# CDCEmu_Logic_v2_1.net
KiCad netlist of a schematic drawn in EAGLE
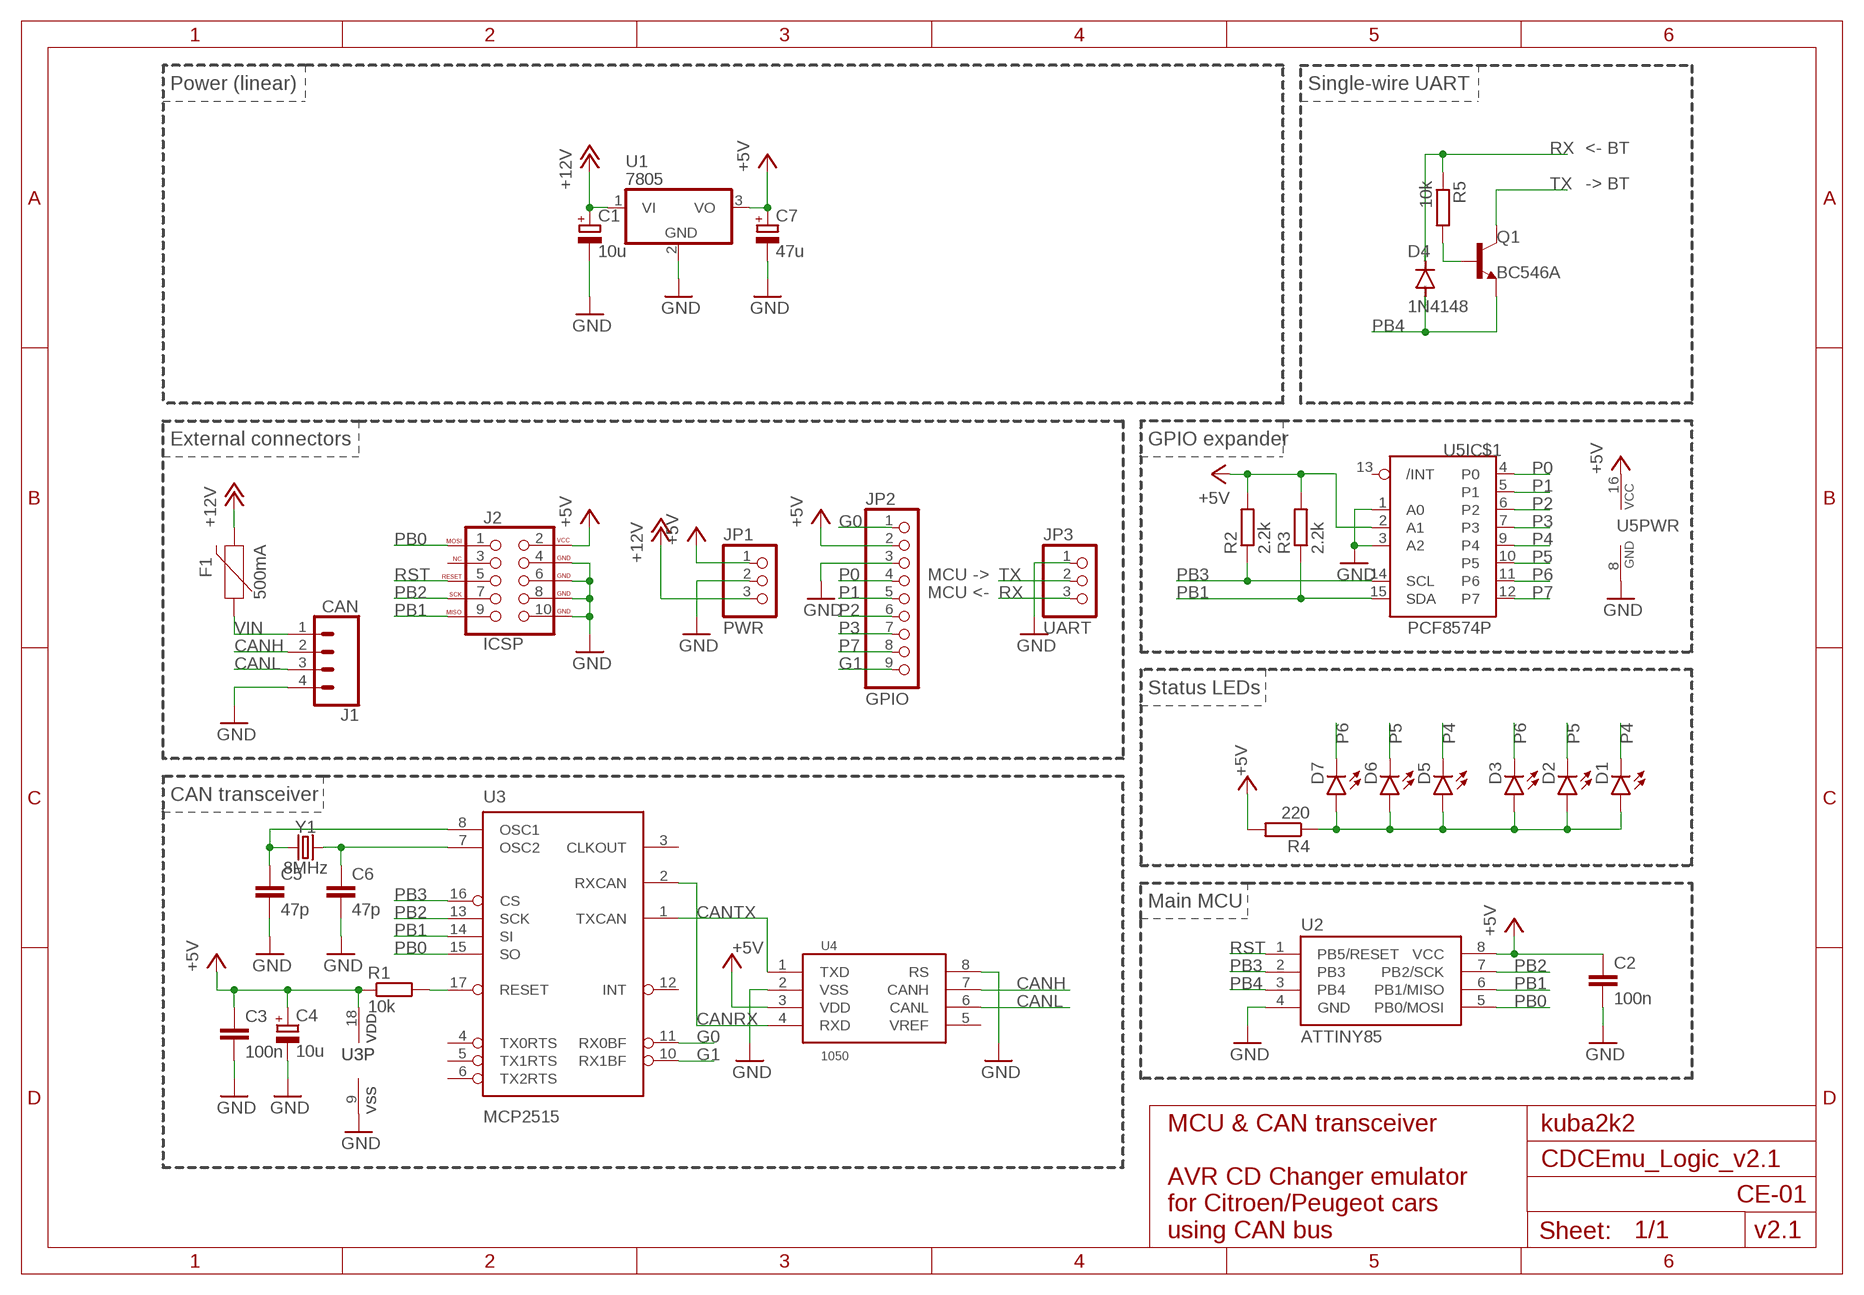
[diagram p0: schematic, sheet 1]

(export (version "E")
  (design (tool "Eeschema 10.0.6"))
  (components
    (comp (ref "C1")
      (value "10u")
      (footprint "eagle-import:C2512-POL")
      (libsource (lib "eagle-import") (part "CPOL-EUC2512"))
    )
    (comp (ref "C2")
      (value "100n")
      (footprint "eagle-import:C050-024X044")
      (libsource (lib "eagle-import") (part "C-EU050-024X044"))
    )
    (comp (ref "C3")
      (value "100n")
      (footprint "eagle-import:C050-024X044")
      (libsource (lib "eagle-import") (part "C-EU050-024X044"))
    )
    (comp (ref "C4")
      (value "10u")
      (footprint "eagle-import:E2,5-6")
      (libsource (lib "eagle-import") (part "CPOL-EUE2.5-6"))
    )
    (comp (ref "C5")
      (value "47p")
      (footprint "eagle-import:C0805")
      (libsource (lib "eagle-import") (part "C-EUC0805"))
    )
    (comp (ref "C6")
      (value "47p")
      (footprint "eagle-import:C0805")
      (libsource (lib "eagle-import") (part "C-EUC0805"))
    )
    (comp (ref "C7")
      (value "47u")
      (footprint "eagle-import:C2512-POL")
      (libsource (lib "eagle-import") (part "CPOL-EUC2512"))
    )
    (comp (ref "D1")
      (value "LED3MM")
      (footprint "eagle-import:LED3MM")
      (libsource (lib "eagle-import") (part "LED3MM"))
    )
    (comp (ref "D2")
      (value "LED3MM")
      (footprint "eagle-import:LED3MM")
      (libsource (lib "eagle-import") (part "LED3MM"))
    )
    (comp (ref "D3")
      (value "LED3MM")
      (footprint "eagle-import:LED3MM")
      (libsource (lib "eagle-import") (part "LED3MM"))
    )
    (comp (ref "D4")
      (value "1N4148")
      (footprint "eagle-import:DO35-7")
      (libsource (lib "eagle-import") (part "1N4148DO35-7"))
    )
    (comp (ref "D5")
      (value "LEDCHIP-LED0805")
      (footprint "eagle-import:CHIP-LED0805")
      (libsource (lib "eagle-import") (part "LEDCHIP-LED0805"))
    )
    (comp (ref "D6")
      (value "LEDCHIP-LED0805")
      (footprint "eagle-import:CHIP-LED0805")
      (libsource (lib "eagle-import") (part "LEDCHIP-LED0805"))
    )
    (comp (ref "D7")
      (value "LEDCHIP-LED0805")
      (footprint "eagle-import:CHIP-LED0805")
      (libsource (lib "eagle-import") (part "LEDCHIP-LED0805"))
    )
    (comp (ref "F1")
      (value "500mA")
      (footprint "eagle-import:1812")
      (libsource (lib "eagle-import") (part "PPTC_16V_2.5A"))
    )
    (comp (ref "J1")
      (value "CAN")
      (footprint "eagle-import:JST-4-PTH")
      (libsource (lib "eagle-import") (part "CONN_04JST-PTH"))
    )
    (comp (ref "J2")
      (value "ICSP")
      (footprint "eagle-import:2X5-SHROUDED_LOCK")
      (libsource (lib "eagle-import") (part "AVR_SPI_PROG_5X2LOCK"))
    )
    (comp (ref "JP1")
      (value "PWR")
      (footprint "eagle-import:1X03")
      (libsource (lib "eagle-import") (part "PINHD-1X3"))
    )
    (comp (ref "JP2")
      (value "GPIO")
      (footprint "eagle-import:1X09")
      (libsource (lib "eagle-import") (part "PINHD-1X9"))
    )
    (comp (ref "JP3")
      (value "UART")
      (footprint "eagle-import:1X03")
      (libsource (lib "eagle-import") (part "PINHD-1X3"))
    )
    (comp (ref "Q1")
      (value "BC546A")
      (footprint "eagle-import:TO92-EBC")
      (libsource (lib "eagle-import") (part "BC546A"))
    )
    (comp (ref "R1")
      (value "10k")
      (footprint "eagle-import:R0805")
      (libsource (lib "eagle-import") (part "R-EU_R0805"))
    )
    (comp (ref "R2")
      (value "2.2k")
      (footprint "eagle-import:R0805")
      (libsource (lib "eagle-import") (part "R-EU_R0805"))
    )
    (comp (ref "R3")
      (value "2.2k")
      (footprint "eagle-import:R0805")
      (libsource (lib "eagle-import") (part "R-EU_R0805"))
    )
    (comp (ref "R4")
      (value "220")
      (footprint "eagle-import:0204_7")
      (libsource (lib "eagle-import") (part "R-EU_0204/7"))
    )
    (comp (ref "R5")
      (value "10k")
      (footprint "eagle-import:0204_7")
      (libsource (lib "eagle-import") (part "R-EU_0204/7"))
    )
    (comp (ref "U1")
      (value "7805")
      (footprint "eagle-import:TO220H-NOHOLE")
      (libsource (lib "eagle-import") (part "78T-NOHOLE"))
    )
    (comp (ref "U2")
      (value "ATTINY85")
      (footprint "eagle-import:PDIP08_300MIL")
      (libsource (lib "eagle-import") (part "ATTINY85P-"))
    )
    (comp (ref "U3")
      (value "MCP2515")
      (footprint "eagle-import:SO18W")
      (libsource (lib "eagle-import") (part "MCP2515(MCP2510)SO"))
    )
    (comp (ref "U4")
      (value "1050")
      (footprint "eagle-import:SO08")
      (libsource (lib "eagle-import") (part "TJA1050"))
    )
    (comp (ref "U5")
      (value "PCF8574P")
      (footprint "eagle-import:DIL16")
      (libsource (lib "eagle-import") (part "PCF8574P"))
    )
    (comp (ref "Y1")
      (value "8MHz")
      (footprint "eagle-import:HC49U")
      (libsource (lib "eagle-import") (part "CRYSTALPTH-HC49UV"))
    )
  )
  (nets
    (net (code "1") (name "+5V") (class "Default")
      (node (ref "C2") (pin "1") (pinfunction "1_1") (pintype "passive"))
      (node (ref "C3") (pin "1") (pinfunction "1_1") (pintype "passive"))
      (node (ref "C4") (pin "+") (pinfunction "+_+") (pintype "passive"))
      (node (ref "C7") (pin "+") (pinfunction "+_+") (pintype "passive"))
      (node (ref "J2") (pin "2") (pinfunction "VCC_2") (pintype "power_in"))
      (node (ref "JP1") (pin "1") (pinfunction "1_1") (pintype "passive"))
      (node (ref "JP2") (pin "2") (pinfunction "2_2") (pintype "passive"))
      (node (ref "R1") (pin "1") (pinfunction "1_1") (pintype "passive"))
      (node (ref "R2") (pin "2") (pinfunction "2_2") (pintype "passive"))
      (node (ref "R3") (pin "2") (pinfunction "2_2") (pintype "passive"))
      (node (ref "R4") (pin "2") (pinfunction "2_2") (pintype "passive"))
      (node (ref "U1") (pin "3") (pinfunction "VO_3") (pintype "passive"))
      (node (ref "U2") (pin "8") (pinfunction "VCC_8") (pintype "power_in"))
      (node (ref "U3") (pin "18") (pinfunction "VDD_18") (pintype "power_in"))
      (node (ref "U4") (pin "3") (pinfunction "VDD_3") (pintype "power_in"))
      (node (ref "U5") (pin "16") (pinfunction "VCC_16") (pintype "power_in"))
      (node (ref "U5") (pin "2") (pinfunction "A1_2") (pintype "input"))
    )
    (net (code "2") (name "+12V") (class "Default")
      (node (ref "C1") (pin "+") (pinfunction "+_+") (pintype "passive"))
      (node (ref "F1") (pin "2") (pinfunction "2_2") (pintype "bidirectional"))
      (node (ref "JP1") (pin "3") (pinfunction "3_3") (pintype "passive"))
      (node (ref "U1") (pin "1") (pinfunction "VI_1") (pintype "input"))
    )
    (net (code "3") (name "/CANH") (class "Default")
      (node (ref "J1") (pin "2") (pinfunction "2_2") (pintype "passive"))
      (node (ref "U4") (pin "7") (pinfunction "CANH_7") (pintype "bidirectional"))
    )
    (net (code "4") (name "/CANL") (class "Default")
      (node (ref "J1") (pin "3") (pinfunction "3_3") (pintype "passive"))
      (node (ref "U4") (pin "6") (pinfunction "CANL_6") (pintype "bidirectional"))
    )
    (net (code "5") (name "/CANRX") (class "Default")
      (node (ref "U3") (pin "2") (pinfunction "RXCAN_2") (pintype "input"))
      (node (ref "U4") (pin "4") (pinfunction "RXD_4") (pintype "output"))
    )
    (net (code "6") (name "/CANTX") (class "Default")
      (node (ref "U3") (pin "1") (pinfunction "TXCAN_1") (pintype "output"))
      (node (ref "U4") (pin "1") (pinfunction "TXD_1") (pintype "input"))
    )
    (net (code "7") (name "/G0") (class "Default")
      (node (ref "JP2") (pin "1") (pinfunction "1_1") (pintype "passive"))
      (node (ref "U3") (pin "11") (pinfunction "RX0BF_11") (pintype "output"))
    )
    (net (code "8") (name "/G1") (class "Default")
      (node (ref "JP2") (pin "9") (pinfunction "9_9") (pintype "passive"))
      (node (ref "U3") (pin "10") (pinfunction "RX1BF_10") (pintype "output"))
    )
    (net (code "9") (name "/P0") (class "Default")
      (node (ref "JP2") (pin "4") (pinfunction "4_4") (pintype "passive"))
      (node (ref "U5") (pin "4") (pinfunction "P0_4") (pintype "bidirectional"))
    )
    (net (code "10") (name "/P1") (class "Default")
      (node (ref "JP2") (pin "5") (pinfunction "5_5") (pintype "passive"))
      (node (ref "U5") (pin "5") (pinfunction "P1_5") (pintype "bidirectional"))
    )
    (net (code "11") (name "/P2") (class "Default")
      (node (ref "JP2") (pin "6") (pinfunction "6_6") (pintype "passive"))
      (node (ref "U5") (pin "6") (pinfunction "P2_6") (pintype "bidirectional"))
    )
    (net (code "12") (name "/P3") (class "Default")
      (node (ref "JP2") (pin "7") (pinfunction "7_7") (pintype "passive"))
      (node (ref "U5") (pin "7") (pinfunction "P3_7") (pintype "bidirectional"))
    )
    (net (code "13") (name "/P4") (class "Default")
      (node (ref "D1") (pin "K") (pinfunction "C_K") (pintype "passive"))
      (node (ref "D5") (pin "C") (pinfunction "C_C") (pintype "passive"))
      (node (ref "U5") (pin "9") (pinfunction "P4_9") (pintype "bidirectional"))
    )
    (net (code "14") (name "/P5") (class "Default")
      (node (ref "D2") (pin "K") (pinfunction "C_K") (pintype "passive"))
      (node (ref "D6") (pin "C") (pinfunction "C_C") (pintype "passive"))
      (node (ref "U5") (pin "10") (pinfunction "P5_10") (pintype "bidirectional"))
    )
    (net (code "15") (name "/P6") (class "Default")
      (node (ref "D3") (pin "K") (pinfunction "C_K") (pintype "passive"))
      (node (ref "D7") (pin "C") (pinfunction "C_C") (pintype "passive"))
      (node (ref "U5") (pin "11") (pinfunction "P6_11") (pintype "bidirectional"))
    )
    (net (code "16") (name "/P7") (class "Default")
      (node (ref "JP2") (pin "8") (pinfunction "8_8") (pintype "passive"))
      (node (ref "U5") (pin "12") (pinfunction "P7_12") (pintype "bidirectional"))
    )
    (net (code "17") (name "/PB0") (class "Default")
      (node (ref "J2") (pin "1") (pinfunction "MOSI_1") (pintype "passive"))
      (node (ref "U2") (pin "5") (pinfunction "PB0/MOSI_5") (pintype "bidirectional"))
      (node (ref "U3") (pin "15") (pinfunction "SO_15") (pintype "output"))
    )
    (net (code "18") (name "/PB1") (class "Default")
      (node (ref "J2") (pin "9") (pinfunction "MISO_9") (pintype "passive"))
      (node (ref "R3") (pin "1") (pinfunction "1_1") (pintype "passive"))
      (node (ref "U2") (pin "6") (pinfunction "PB1/MISO_6") (pintype "bidirectional"))
      (node (ref "U3") (pin "14") (pinfunction "SI_14") (pintype "input"))
      (node (ref "U5") (pin "15") (pinfunction "SDA_15") (pintype "bidirectional"))
    )
    (net (code "19") (name "/PB2") (class "Default")
      (node (ref "J2") (pin "7") (pinfunction "SCK_7") (pintype "passive"))
      (node (ref "U2") (pin "7") (pinfunction "PB2/SCK_7") (pintype "bidirectional"))
      (node (ref "U3") (pin "13") (pinfunction "SCK_13") (pintype "input"))
    )
    (net (code "20") (name "/PB3") (class "Default")
      (node (ref "R2") (pin "1") (pinfunction "1_1") (pintype "passive"))
      (node (ref "U2") (pin "2") (pinfunction "PB3_2") (pintype "bidirectional"))
      (node (ref "U3") (pin "16") (pinfunction "CS_16") (pintype "input"))
      (node (ref "U5") (pin "14") (pinfunction "SCL_14") (pintype "input"))
    )
    (net (code "21") (name "/PB4") (class "Default")
      (node (ref "D4") (pin "A") (pinfunction "A_A") (pintype "passive"))
      (node (ref "Q1") (pin "E") (pinfunction "E_E") (pintype "passive"))
      (node (ref "U2") (pin "3") (pinfunction "PB4_3") (pintype "bidirectional"))
    )
    (net (code "22") (name "/RST") (class "Default")
      (node (ref "J2") (pin "5") (pinfunction "RESET_5") (pintype "passive"))
      (node (ref "U2") (pin "1") (pinfunction "PB5/RESET_1") (pintype "bidirectional"))
    )
    (net (code "23") (name "/RX") (class "Default")
      (node (ref "D4") (pin "C") (pinfunction "C_C") (pintype "passive"))
      (node (ref "JP3") (pin "3") (pinfunction "3_3") (pintype "passive"))
      (node (ref "R5") (pin "1") (pinfunction "1_1") (pintype "passive"))
    )
    (net (code "24") (name "/TX") (class "Default")
      (node (ref "JP3") (pin "2") (pinfunction "2_2") (pintype "passive"))
      (node (ref "Q1") (pin "C") (pinfunction "C_C") (pintype "passive"))
    )
    (net (code "25") (name "/VIN") (class "Default")
      (node (ref "F1") (pin "1") (pinfunction "1_1") (pintype "bidirectional"))
      (node (ref "J1") (pin "1") (pinfunction "1_1") (pintype "passive"))
    )
    (net (code "26") (name "GND") (class "Default")
      (node (ref "C1") (pin "-") (pinfunction "-_-") (pintype "passive"))
      (node (ref "C2") (pin "2") (pinfunction "2_2") (pintype "passive"))
      (node (ref "C3") (pin "2") (pinfunction "2_2") (pintype "passive"))
      (node (ref "C4") (pin "-") (pinfunction "-_-") (pintype "passive"))
      (node (ref "C5") (pin "2") (pinfunction "2_2") (pintype "passive"))
      (node (ref "C6") (pin "2") (pinfunction "2_2") (pintype "passive"))
      (node (ref "C7") (pin "-") (pinfunction "-_-") (pintype "passive"))
      (node (ref "J1") (pin "4") (pinfunction "4_4") (pintype "passive"))
      (node (ref "J2") (pin "10") (pinfunction "GND_10") (pintype "power_in"))
      (node (ref "J2") (pin "4") (pinfunction "GND_4") (pintype "power_in"))
      (node (ref "J2") (pin "6") (pinfunction "GND_6") (pintype "power_in"))
      (node (ref "J2") (pin "8") (pinfunction "GND_8") (pintype "power_in"))
      (node (ref "JP1") (pin "2") (pinfunction "2_2") (pintype "passive"))
      (node (ref "JP2") (pin "3") (pinfunction "3_3") (pintype "passive"))
      (node (ref "JP3") (pin "1") (pinfunction "1_1") (pintype "passive"))
      (node (ref "U1") (pin "2") (pinfunction "GND_2") (pintype "passive"))
      (node (ref "U2") (pin "4") (pinfunction "GND_4") (pintype "power_in"))
      (node (ref "U3") (pin "9") (pinfunction "VSS_9") (pintype "power_in"))
      (node (ref "U4") (pin "2") (pinfunction "VSS_2") (pintype "power_in"))
      (node (ref "U4") (pin "8") (pinfunction "RS_8") (pintype "input"))
      (node (ref "U5") (pin "1") (pinfunction "A0_1") (pintype "input"))
      (node (ref "U5") (pin "3") (pinfunction "A2_3") (pintype "input"))
      (node (ref "U5") (pin "8") (pinfunction "GND_8") (pintype "power_in"))
    )
    (net (code "27") (name "Net-(D1-PadA)") (class "Default")
      (node (ref "D1") (pin "A") (pinfunction "A_A") (pintype "passive"))
      (node (ref "D2") (pin "A") (pinfunction "A_A") (pintype "passive"))
      (node (ref "D3") (pin "A") (pinfunction "A_A") (pintype "passive"))
      (node (ref "D5") (pin "A") (pinfunction "A_A") (pintype "passive"))
      (node (ref "D6") (pin "A") (pinfunction "A_A") (pintype "passive"))
      (node (ref "D7") (pin "A") (pinfunction "A_A") (pintype "passive"))
      (node (ref "R4") (pin "1") (pinfunction "1_1") (pintype "passive"))
    )
    (net (code "28") (name "Net-(Q1-PadB)") (class "Default")
      (node (ref "Q1") (pin "B") (pinfunction "B_B") (pintype "passive"))
      (node (ref "R5") (pin "2") (pinfunction "2_2") (pintype "passive"))
    )
    (net (code "29") (name "Net-(U3A-OSC1)") (class "Default")
      (node (ref "C5") (pin "1") (pinfunction "1_1") (pintype "passive"))
      (node (ref "U3") (pin "8") (pinfunction "OSC1_8") (pintype "input"))
      (node (ref "Y1") (pin "1") (pinfunction "1_1") (pintype "passive"))
    )
    (net (code "30") (name "Net-(U3A-OSC2)") (class "Default")
      (node (ref "C6") (pin "1") (pinfunction "1_1") (pintype "passive"))
      (node (ref "U3") (pin "7") (pinfunction "OSC2_7") (pintype "output"))
      (node (ref "Y1") (pin "2") (pinfunction "2_2") (pintype "passive"))
    )
    (net (code "31") (name "Net-(U3A-RESET)") (class "Default")
      (node (ref "R1") (pin "2") (pinfunction "2_2") (pintype "passive"))
      (node (ref "U3") (pin "17") (pinfunction "RESET_17") (pintype "input"))
    )
    (net (code "32") (name "unconnected-(J2-NC-Pad3)") (class "Default")
      (node (ref "J2") (pin "3") (pinfunction "NC_3") (pintype "no_connect"))
    )
    (net (code "33") (name "unconnected-(U3A-CLKOUT-Pad3)") (class "Default")
      (node (ref "U3") (pin "3") (pinfunction "CLKOUT_3") (pintype "output"))
    )
    (net (code "34") (name "unconnected-(U3A-INT-Pad12)") (class "Default")
      (node (ref "U3") (pin "12") (pinfunction "INT_12") (pintype "output"))
    )
    (net (code "35") (name "unconnected-(U3A-TX0RTS-Pad4)") (class "Default")
      (node (ref "U3") (pin "4") (pinfunction "TX0RTS_4") (pintype "input"))
    )
    (net (code "36") (name "unconnected-(U3A-TX1RTS-Pad5)") (class "Default")
      (node (ref "U3") (pin "5") (pinfunction "TX1RTS_5") (pintype "input"))
    )
    (net (code "37") (name "unconnected-(U3A-TX2RTS-Pad6)") (class "Default")
      (node (ref "U3") (pin "6") (pinfunction "TX2RTS_6") (pintype "input"))
    )
    (net (code "38") (name "unconnected-(U4-VREF-Pad5)") (class "Default")
      (node (ref "U4") (pin "5") (pinfunction "VREF_5") (pintype "passive"))
    )
    (net (code "39") (name "unconnected-(U5A-{slash}INT-Pad13)") (class "Default")
      (node (ref "U5") (pin "13") (pinfunction "/INT_13") (pintype "output"))
    )
  )
)
